# 7SEG_4DIGIT_1.net
KiCad netlist of a schematic drawn in EAGLE
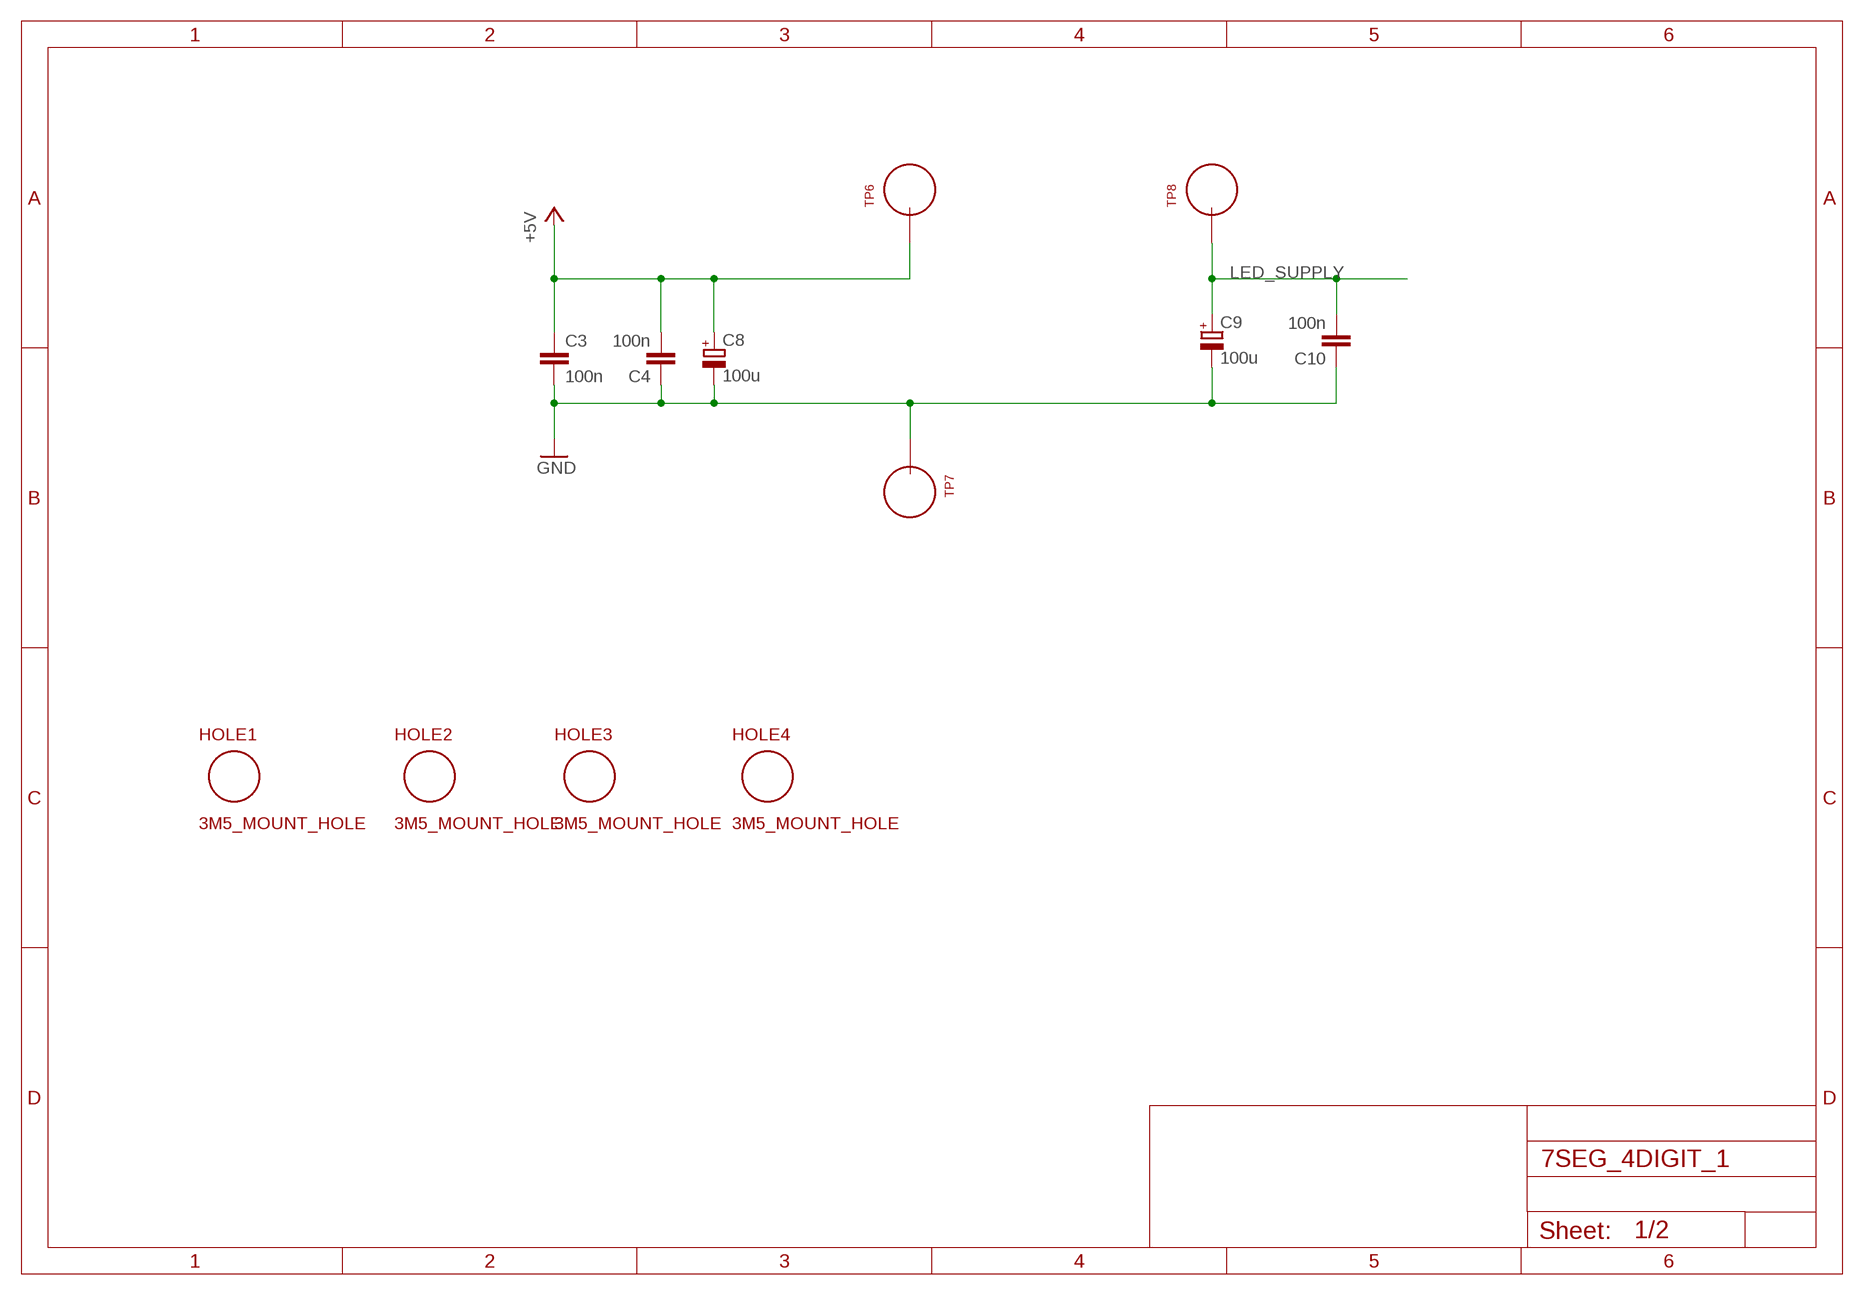
[diagram p0: schematic, sheet 1]
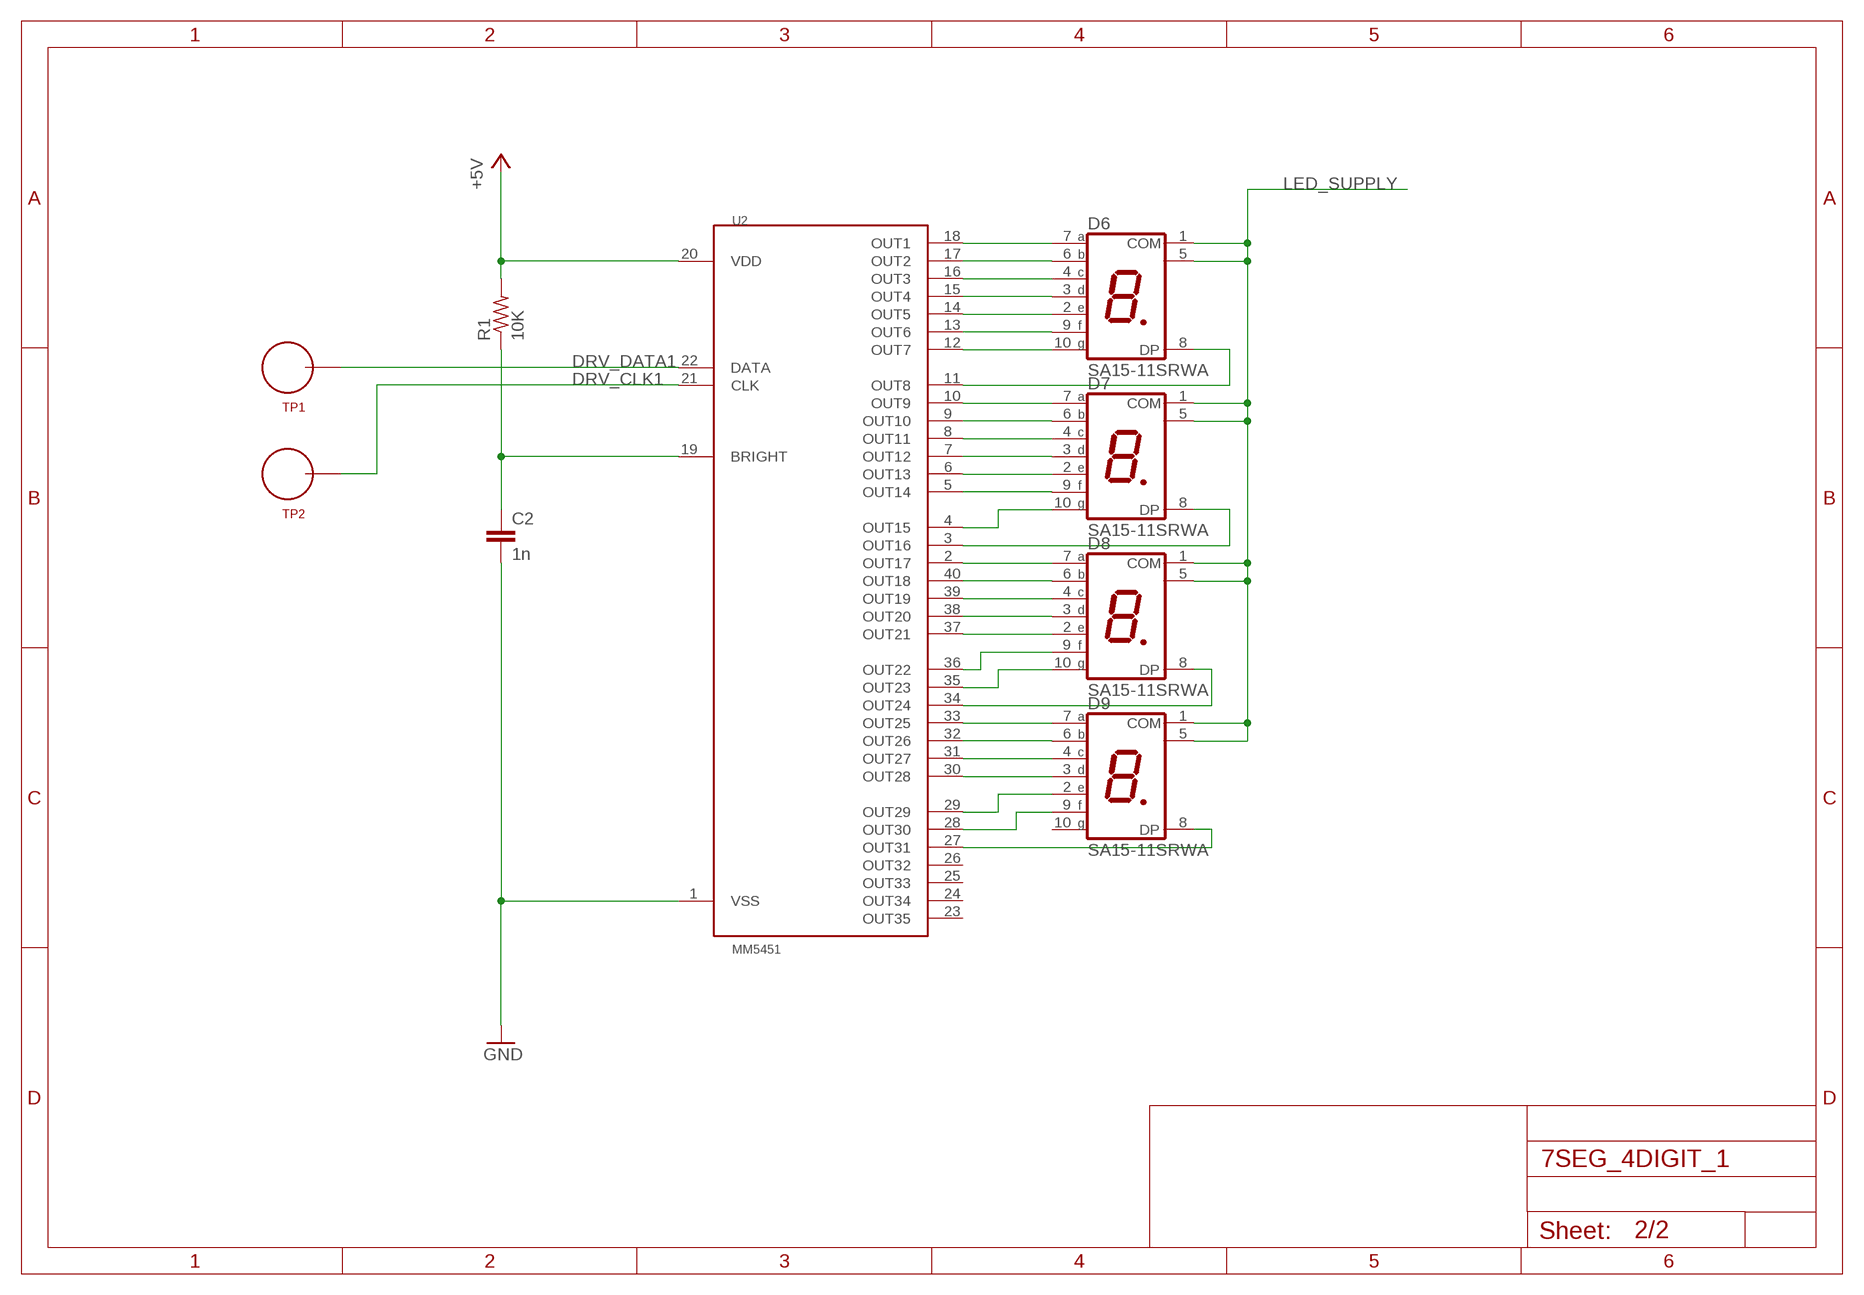
[diagram p1: schematic, sheet 2]

(export (version "E")
  (design (tool "Eeschema 10.0.6"))
  (components
    (comp (ref "C2")
      (value "1n")
      (footprint "eagle-import:CAP_P2INCH")
      (libsource (lib "eagle-import") (part "C_P2INCH"))
    )
    (comp (ref "D6")
      (value "SA15-11SRWA")
      (footprint "eagle-import:SC15")
      (libsource (lib "eagle-import") (part "SA15-11SRWA"))
    )
    (comp (ref "D7")
      (value "SA15-11SRWA")
      (footprint "eagle-import:SC15")
      (libsource (lib "eagle-import") (part "SA15-11SRWA"))
    )
    (comp (ref "D8")
      (value "SA15-11SRWA")
      (footprint "eagle-import:SC15")
      (libsource (lib "eagle-import") (part "SA15-11SRWA"))
    )
    (comp (ref "D9")
      (value "SA15-11SRWA")
      (footprint "eagle-import:SC15")
      (libsource (lib "eagle-import") (part "SA15-11SRWA"))
    )
    (comp (ref "R1")
      (value "10K")
      (footprint "eagle-import:R_P2INCH")
      (libsource (lib "eagle-import") (part "R_P2INCH"))
    )
    (comp (ref "TP1")
      (value "TEST_LOOP")
      (footprint "eagle-import:TEST_LOOP")
      (libsource (lib "eagle-import") (part "TEST_LOOP"))
    )
    (comp (ref "TP2")
      (value "TEST_LOOP")
      (footprint "eagle-import:TEST_LOOP")
      (libsource (lib "eagle-import") (part "TEST_LOOP"))
    )
    (comp (ref "U2")
      (value "MM5451")
      (footprint "eagle-import:DIP40_P6")
      (libsource (lib "eagle-import") (part "MM5451"))
    )
    (comp (ref "C3")
      (value "100n")
      (footprint "eagle-import:CAP_P2INCH")
      (libsource (lib "eagle-import") (part "C_P2INCH"))
    )
    (comp (ref "C4")
      (value "100n")
      (footprint "eagle-import:CAP_P2INCH")
      (libsource (lib "eagle-import") (part "C_P2INCH"))
    )
    (comp (ref "C8")
      (value "100u")
      (footprint "eagle-import:POLARISED_CAP_2P5_6P3MM")
      (libsource (lib "eagle-import") (part "POLARISED_CAP_2P5_6P3MM"))
    )
    (comp (ref "C9")
      (value "100u")
      (footprint "eagle-import:POLARISED_CAP_2P5_6P3MM")
      (libsource (lib "eagle-import") (part "POLARISED_CAP_2P5_6P3MM"))
    )
    (comp (ref "C10")
      (value "100n")
      (footprint "eagle-import:CAP_P2INCH")
      (libsource (lib "eagle-import") (part "C_P2INCH"))
    )
    (comp (ref "HOLE1")
      (value "3M5_MOUNT_HOLE")
      (footprint "eagle-import:3P5M_HOLE")
      (libsource (lib "eagle-import") (part "3M5_MOUNT_HOLE"))
    )
    (comp (ref "HOLE2")
      (value "3M5_MOUNT_HOLE")
      (footprint "eagle-import:3P5M_HOLE")
      (libsource (lib "eagle-import") (part "3M5_MOUNT_HOLE"))
    )
    (comp (ref "HOLE3")
      (value "3M5_MOUNT_HOLE")
      (footprint "eagle-import:3P5M_HOLE")
      (libsource (lib "eagle-import") (part "3M5_MOUNT_HOLE"))
    )
    (comp (ref "HOLE4")
      (value "3M5_MOUNT_HOLE")
      (footprint "eagle-import:3P5M_HOLE")
      (libsource (lib "eagle-import") (part "3M5_MOUNT_HOLE"))
    )
    (comp (ref "TP6")
      (value "TEST_LOOP")
      (footprint "eagle-import:TEST_LOOP")
      (libsource (lib "eagle-import") (part "TEST_LOOP"))
    )
    (comp (ref "TP7")
      (value "TEST_LOOP")
      (footprint "eagle-import:TEST_LOOP")
      (libsource (lib "eagle-import") (part "TEST_LOOP"))
    )
    (comp (ref "TP8")
      (value "TEST_LOOP")
      (footprint "eagle-import:TEST_LOOP")
      (libsource (lib "eagle-import") (part "TEST_LOOP"))
    )
  )
  (nets
    (net (code "1") (name "+5V") (class "Default")
      (node (ref "C3") (pin "1") (pinfunction "1_1") (pintype "passive"))
      (node (ref "C4") (pin "2") (pinfunction "2_2") (pintype "passive"))
      (node (ref "C8") (pin "A") (pinfunction "A_A") (pintype "passive"))
      (node (ref "R1") (pin "2") (pinfunction "2_2") (pintype "passive"))
      (node (ref "TP6") (pin "P$1") (pinfunction "P$1_P$1") (pintype "bidirectional"))
      (node (ref "U2") (pin "20") (pinfunction "VDD_20") (pintype "power_in"))
    )
    (net (code "2") (name "DRV_CLK1") (class "Default")
      (node (ref "TP2") (pin "P$1") (pinfunction "P$1_P$1") (pintype "bidirectional"))
      (node (ref "U2") (pin "21") (pinfunction "CLK_21") (pintype "input"))
    )
    (net (code "3") (name "DRV_DATA1") (class "Default")
      (node (ref "TP1") (pin "P$1") (pinfunction "P$1_P$1") (pintype "bidirectional"))
      (node (ref "U2") (pin "22") (pinfunction "DATA_22") (pintype "input"))
    )
    (net (code "4") (name "GND") (class "Default")
      (node (ref "C10") (pin "1") (pinfunction "1_1") (pintype "passive"))
      (node (ref "C2") (pin "2") (pinfunction "2_2") (pintype "passive"))
      (node (ref "C3") (pin "2") (pinfunction "2_2") (pintype "passive"))
      (node (ref "C4") (pin "1") (pinfunction "1_1") (pintype "passive"))
      (node (ref "C8") (pin "K") (pinfunction "K_K") (pintype "passive"))
      (node (ref "C9") (pin "K") (pinfunction "K_K") (pintype "passive"))
      (node (ref "TP7") (pin "P$1") (pinfunction "P$1_P$1") (pintype "bidirectional"))
      (node (ref "U2") (pin "1") (pinfunction "VSS_1") (pintype "power_in"))
    )
    (net (code "5") (name "LED_SUPPLY") (class "Default")
      (node (ref "C10") (pin "2") (pinfunction "2_2") (pintype "passive"))
      (node (ref "C9") (pin "A") (pinfunction "A_A") (pintype "passive"))
      (node (ref "D6") (pin "1") (pinfunction "COM_1") (pintype "passive"))
      (node (ref "D6") (pin "5") (pinfunction "COM_5") (pintype "passive"))
      (node (ref "D7") (pin "1") (pinfunction "COM_1") (pintype "passive"))
      (node (ref "D7") (pin "5") (pinfunction "COM_5") (pintype "passive"))
      (node (ref "D8") (pin "1") (pinfunction "COM_1") (pintype "passive"))
      (node (ref "D8") (pin "5") (pinfunction "COM_5") (pintype "passive"))
      (node (ref "D9") (pin "1") (pinfunction "COM_1") (pintype "passive"))
      (node (ref "D9") (pin "5") (pinfunction "COM_5") (pintype "passive"))
      (node (ref "TP8") (pin "P$1") (pinfunction "P$1_P$1") (pintype "bidirectional"))
    )
    (net (code "6") (name "Net-(D6-A)") (class "Default")
      (node (ref "D6") (pin "7") (pinfunction "A_7") (pintype "passive"))
      (node (ref "U2") (pin "18") (pinfunction "OUT1_18") (pintype "output"))
    )
    (net (code "7") (name "Net-(D6-B)") (class "Default")
      (node (ref "D6") (pin "6") (pinfunction "B_6") (pintype "passive"))
      (node (ref "U2") (pin "17") (pinfunction "OUT2_17") (pintype "output"))
    )
    (net (code "8") (name "Net-(D6-C)") (class "Default")
      (node (ref "D6") (pin "4") (pinfunction "C_4") (pintype "passive"))
      (node (ref "U2") (pin "16") (pinfunction "OUT3_16") (pintype "output"))
    )
    (net (code "9") (name "Net-(D6-D)") (class "Default")
      (node (ref "D6") (pin "3") (pinfunction "D_3") (pintype "passive"))
      (node (ref "U2") (pin "15") (pinfunction "OUT4_15") (pintype "output"))
    )
    (net (code "10") (name "Net-(D6-DP)") (class "Default")
      (node (ref "D6") (pin "8") (pinfunction "DP_8") (pintype "passive"))
      (node (ref "U2") (pin "11") (pinfunction "OUT8_11") (pintype "output"))
    )
    (net (code "11") (name "Net-(D6-E)") (class "Default")
      (node (ref "D6") (pin "2") (pinfunction "E_2") (pintype "passive"))
      (node (ref "U2") (pin "14") (pinfunction "OUT5_14") (pintype "output"))
    )
    (net (code "12") (name "Net-(D6-F)") (class "Default")
      (node (ref "D6") (pin "9") (pinfunction "F_9") (pintype "passive"))
      (node (ref "U2") (pin "13") (pinfunction "OUT6_13") (pintype "output"))
    )
    (net (code "13") (name "Net-(D6-G)") (class "Default")
      (node (ref "D6") (pin "10") (pinfunction "G_10") (pintype "passive"))
      (node (ref "U2") (pin "12") (pinfunction "OUT7_12") (pintype "output"))
    )
    (net (code "14") (name "Net-(D7-A)") (class "Default")
      (node (ref "D7") (pin "7") (pinfunction "A_7") (pintype "passive"))
      (node (ref "U2") (pin "10") (pinfunction "OUT9_10") (pintype "output"))
    )
    (net (code "15") (name "Net-(D7-B)") (class "Default")
      (node (ref "D7") (pin "6") (pinfunction "B_6") (pintype "passive"))
      (node (ref "U2") (pin "9") (pinfunction "OUT10_9") (pintype "output"))
    )
    (net (code "16") (name "Net-(D7-C)") (class "Default")
      (node (ref "D7") (pin "4") (pinfunction "C_4") (pintype "passive"))
      (node (ref "U2") (pin "8") (pinfunction "OUT11_8") (pintype "output"))
    )
    (net (code "17") (name "Net-(D7-D)") (class "Default")
      (node (ref "D7") (pin "3") (pinfunction "D_3") (pintype "passive"))
      (node (ref "U2") (pin "7") (pinfunction "OUT12_7") (pintype "output"))
    )
    (net (code "18") (name "Net-(D7-DP)") (class "Default")
      (node (ref "D7") (pin "8") (pinfunction "DP_8") (pintype "passive"))
      (node (ref "U2") (pin "3") (pinfunction "OUT16_3") (pintype "output"))
    )
    (net (code "19") (name "Net-(D7-E)") (class "Default")
      (node (ref "D7") (pin "2") (pinfunction "E_2") (pintype "passive"))
      (node (ref "U2") (pin "6") (pinfunction "OUT13_6") (pintype "output"))
    )
    (net (code "20") (name "Net-(D7-F)") (class "Default")
      (node (ref "D7") (pin "9") (pinfunction "F_9") (pintype "passive"))
      (node (ref "U2") (pin "5") (pinfunction "OUT14_5") (pintype "output"))
    )
    (net (code "21") (name "Net-(D7-G)") (class "Default")
      (node (ref "D7") (pin "10") (pinfunction "G_10") (pintype "passive"))
      (node (ref "U2") (pin "4") (pinfunction "OUT15_4") (pintype "output"))
    )
    (net (code "22") (name "Net-(D8-A)") (class "Default")
      (node (ref "D8") (pin "7") (pinfunction "A_7") (pintype "passive"))
      (node (ref "U2") (pin "2") (pinfunction "OUT17_2") (pintype "output"))
    )
    (net (code "23") (name "Net-(D8-B)") (class "Default")
      (node (ref "D8") (pin "6") (pinfunction "B_6") (pintype "passive"))
      (node (ref "U2") (pin "40") (pinfunction "OUT18_40") (pintype "output"))
    )
    (net (code "24") (name "Net-(D8-C)") (class "Default")
      (node (ref "D8") (pin "4") (pinfunction "C_4") (pintype "passive"))
      (node (ref "U2") (pin "39") (pinfunction "OUT19_39") (pintype "output"))
    )
    (net (code "25") (name "Net-(D8-D)") (class "Default")
      (node (ref "D8") (pin "3") (pinfunction "D_3") (pintype "passive"))
      (node (ref "U2") (pin "38") (pinfunction "OUT20_38") (pintype "output"))
    )
    (net (code "26") (name "Net-(D8-DP)") (class "Default")
      (node (ref "D8") (pin "8") (pinfunction "DP_8") (pintype "passive"))
      (node (ref "U2") (pin "34") (pinfunction "OUT24_34") (pintype "output"))
    )
    (net (code "27") (name "Net-(D8-E)") (class "Default")
      (node (ref "D8") (pin "2") (pinfunction "E_2") (pintype "passive"))
      (node (ref "U2") (pin "37") (pinfunction "OUT21_37") (pintype "output"))
    )
    (net (code "28") (name "Net-(D8-F)") (class "Default")
      (node (ref "D8") (pin "9") (pinfunction "F_9") (pintype "passive"))
      (node (ref "U2") (pin "36") (pinfunction "OUT22_36") (pintype "output"))
    )
    (net (code "29") (name "Net-(D8-G)") (class "Default")
      (node (ref "D8") (pin "10") (pinfunction "G_10") (pintype "passive"))
      (node (ref "U2") (pin "35") (pinfunction "OUT23_35") (pintype "output"))
    )
    (net (code "30") (name "Net-(D9-A)") (class "Default")
      (node (ref "D9") (pin "7") (pinfunction "A_7") (pintype "passive"))
      (node (ref "U2") (pin "33") (pinfunction "OUT25_33") (pintype "output"))
    )
    (net (code "31") (name "Net-(D9-B)") (class "Default")
      (node (ref "D9") (pin "6") (pinfunction "B_6") (pintype "passive"))
      (node (ref "U2") (pin "32") (pinfunction "OUT26_32") (pintype "output"))
    )
    (net (code "32") (name "Net-(D9-C)") (class "Default")
      (node (ref "D9") (pin "4") (pinfunction "C_4") (pintype "passive"))
      (node (ref "U2") (pin "31") (pinfunction "OUT27_31") (pintype "output"))
    )
    (net (code "33") (name "Net-(D9-D)") (class "Default")
      (node (ref "D9") (pin "3") (pinfunction "D_3") (pintype "passive"))
      (node (ref "U2") (pin "30") (pinfunction "OUT28_30") (pintype "output"))
    )
    (net (code "34") (name "Net-(D9-DP)") (class "Default")
      (node (ref "D9") (pin "8") (pinfunction "DP_8") (pintype "passive"))
      (node (ref "U2") (pin "27") (pinfunction "OUT31_27") (pintype "output"))
    )
    (net (code "35") (name "Net-(D9-E)") (class "Default")
      (node (ref "D9") (pin "2") (pinfunction "E_2") (pintype "passive"))
      (node (ref "U2") (pin "29") (pinfunction "OUT29_29") (pintype "output"))
    )
    (net (code "36") (name "Net-(D9-F)") (class "Default")
      (node (ref "D9") (pin "9") (pinfunction "F_9") (pintype "passive"))
      (node (ref "U2") (pin "28") (pinfunction "OUT30_28") (pintype "output"))
    )
    (net (code "37") (name "Net-(U2-BRIGHT)") (class "Default")
      (node (ref "C2") (pin "1") (pinfunction "1_1") (pintype "passive"))
      (node (ref "R1") (pin "1") (pinfunction "1_1") (pintype "passive"))
      (node (ref "U2") (pin "19") (pinfunction "BRIGHT_19") (pintype "input"))
    )
    (net (code "38") (name "unconnected-(D9-G-Pad10)") (class "Default")
      (node (ref "D9") (pin "10") (pinfunction "G_10") (pintype "passive"))
    )
    (net (code "39") (name "unconnected-(U2-OUT32-Pad26)") (class "Default")
      (node (ref "U2") (pin "26") (pinfunction "OUT32_26") (pintype "output"))
    )
    (net (code "40") (name "unconnected-(U2-OUT33-Pad25)") (class "Default")
      (node (ref "U2") (pin "25") (pinfunction "OUT33_25") (pintype "output"))
    )
    (net (code "41") (name "unconnected-(U2-OUT34-Pad24)") (class "Default")
      (node (ref "U2") (pin "24") (pinfunction "OUT34_24") (pintype "output"))
    )
    (net (code "42") (name "unconnected-(U2-OUT35-Pad23)") (class "Default")
      (node (ref "U2") (pin "23") (pinfunction "OUT35_23") (pintype "output"))
    )
  )
)
